# light_bulb_PCB.net
KiCad netlist of a schematic drawn in EAGLE
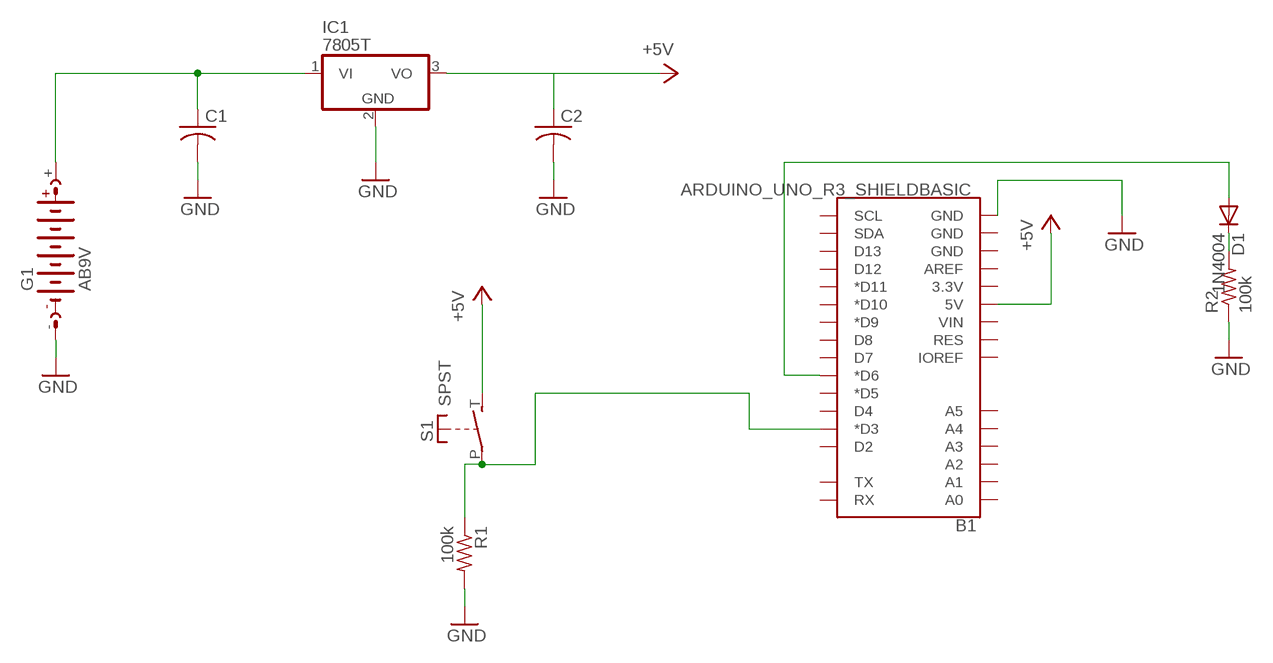
[diagram p0: schematic, sheet 1]

(export (version "E")
  (design (tool "Eeschema 10.0.6"))
  (components
    (comp (ref "B1")
      (value "ARDUINO_UNO_R3_SHIELDBASIC")
      (footprint "eagle-import:UNO_R3_SHIELD")
      (libsource (lib "eagle-import") (part "ARDUINO_UNO_R3_SHIELDBASIC"))
    )
    (comp (ref "C1")
      (value "0.1")
      (footprint "eagle-import:C0805")
      (libsource (lib "eagle-import") (part "C-USC0805"))
    )
    (comp (ref "C2")
      (value "0.1")
      (footprint "eagle-import:C0805")
      (libsource (lib "eagle-import") (part "C-USC0805"))
    )
    (comp (ref "D1")
      (value "1N4004")
      (footprint "eagle-import:DO41-10")
      (libsource (lib "eagle-import") (part "1N4004"))
    )
    (comp (ref "G1")
      (value "AB9V")
      (footprint "eagle-import:AB9V")
      (libsource (lib "eagle-import") (part "AB9V"))
    )
    (comp (ref "IC1")
      (value "7805T")
      (footprint "eagle-import:TO220H")
      (libsource (lib "eagle-import") (part "78T05"))
    )
    (comp (ref "R1")
      (value "100k")
      (footprint "eagle-import:R0805")
      (libsource (lib "eagle-import") (part "R-US_R0805"))
    )
    (comp (ref "R2")
      (value "100k")
      (footprint "eagle-import:R0805")
      (libsource (lib "eagle-import") (part "R-US_R0805"))
    )
    (comp (ref "S1")
      (value "SPST")
      (footprint "eagle-import:JUDCOSPST")
      (libsource (lib "eagle-import") (part "SPST"))
    )
  )
  (nets
    (net (code "1") (name "+5V") (class "Default")
      (node (ref "B1") (pin "5V") (pinfunction "5V_5V") (pintype "bidirectional"))
      (node (ref "C2") (pin "1") (pinfunction "1_1") (pintype "passive"))
      (node (ref "IC1") (pin "3") (pinfunction "VO_3") (pintype "passive"))
      (node (ref "S1") (pin "T") (pinfunction "S_T") (pintype "passive"))
    )
    (net (code "2") (name "GND") (class "Default")
      (node (ref "B1") (pin "GND@0") (pinfunction "GND_GND@0") (pintype "bidirectional"))
      (node (ref "C1") (pin "2") (pinfunction "2_2") (pintype "passive"))
      (node (ref "C2") (pin "2") (pinfunction "2_2") (pintype "passive"))
      (node (ref "G1") (pin "-") (pinfunction "-_-") (pintype "passive"))
      (node (ref "IC1") (pin "2") (pinfunction "GND_2") (pintype "passive"))
      (node (ref "R1") (pin "2") (pinfunction "2_2") (pintype "passive"))
      (node (ref "R2") (pin "1") (pinfunction "1_1") (pintype "passive"))
    )
    (net (code "3") (name "Net-(B1-*D3)") (class "Default")
      (node (ref "B1") (pin "D3") (pinfunction "*D3_D3") (pintype "bidirectional"))
      (node (ref "R1") (pin "1") (pinfunction "1_1") (pintype "passive"))
      (node (ref "S1") (pin "P") (pinfunction "P_P") (pintype "passive"))
    )
    (net (code "4") (name "Net-(B1-*D6)") (class "Default")
      (node (ref "B1") (pin "D6") (pinfunction "*D6_D6") (pintype "bidirectional"))
      (node (ref "D1") (pin "A") (pinfunction "A_A") (pintype "passive"))
    )
    (net (code "5") (name "Net-(D1-PadC)") (class "Default")
      (node (ref "D1") (pin "C") (pinfunction "C_C") (pintype "passive"))
      (node (ref "R2") (pin "2") (pinfunction "2_2") (pintype "passive"))
    )
    (net (code "6") (name "Net-(IC1-VI)") (class "Default")
      (node (ref "C1") (pin "1") (pinfunction "1_1") (pintype "passive"))
      (node (ref "G1") (pin "+") (pinfunction "+_+") (pintype "passive"))
      (node (ref "IC1") (pin "1") (pinfunction "VI_1") (pintype "input"))
    )
    (net (code "7") (name "unconnected-(B1-*D5-PadD5)") (class "Default")
      (node (ref "B1") (pin "D5") (pinfunction "*D5_D5") (pintype "bidirectional"))
    )
    (net (code "8") (name "unconnected-(B1-*D9-PadD9)") (class "Default")
      (node (ref "B1") (pin "D9") (pinfunction "*D9_D9") (pintype "bidirectional"))
    )
    (net (code "9") (name "unconnected-(B1-*D10-PadD10)") (class "Default")
      (node (ref "B1") (pin "D10") (pinfunction "*D10_D10") (pintype "bidirectional"))
    )
    (net (code "10") (name "unconnected-(B1-*D11-PadD11)") (class "Default")
      (node (ref "B1") (pin "D11") (pinfunction "*D11_D11") (pintype "bidirectional"))
    )
    (net (code "11") (name "unconnected-(B1-GND-PadGND@1)") (class "Default")
      (node (ref "B1") (pin "GND@1") (pinfunction "GND_GND@1") (pintype "bidirectional"))
    )
    (net (code "12") (name "unconnected-(B1-GND-PadGND@2)") (class "Default")
      (node (ref "B1") (pin "GND@2") (pinfunction "GND_GND@2") (pintype "bidirectional"))
    )
    (net (code "13") (name "unconnected-(B1-Pad3.3V)") (class "Default")
      (node (ref "B1") (pin "3.3V") (pinfunction "3.3V_3.3V") (pintype "bidirectional"))
    )
    (net (code "14") (name "unconnected-(B1-PadA0)") (class "Default")
      (node (ref "B1") (pin "A0") (pinfunction "A0_A0") (pintype "bidirectional"))
    )
    (net (code "15") (name "unconnected-(B1-PadA1)") (class "Default")
      (node (ref "B1") (pin "A1") (pinfunction "A1_A1") (pintype "bidirectional"))
    )
    (net (code "16") (name "unconnected-(B1-PadA2)") (class "Default")
      (node (ref "B1") (pin "A2") (pinfunction "A2_A2") (pintype "bidirectional"))
    )
    (net (code "17") (name "unconnected-(B1-PadA3)") (class "Default")
      (node (ref "B1") (pin "A3") (pinfunction "A3_A3") (pintype "bidirectional"))
    )
    (net (code "18") (name "unconnected-(B1-PadA4)") (class "Default")
      (node (ref "B1") (pin "A4") (pinfunction "A4_A4") (pintype "bidirectional"))
    )
    (net (code "19") (name "unconnected-(B1-PadA5)") (class "Default")
      (node (ref "B1") (pin "A5") (pinfunction "A5_A5") (pintype "bidirectional"))
    )
    (net (code "20") (name "unconnected-(B1-PadAREF)") (class "Default")
      (node (ref "B1") (pin "AREF") (pinfunction "AREF_AREF") (pintype "bidirectional"))
    )
    (net (code "21") (name "unconnected-(B1-PadD2)") (class "Default")
      (node (ref "B1") (pin "D2") (pinfunction "D2_D2") (pintype "bidirectional"))
    )
    (net (code "22") (name "unconnected-(B1-PadD4)") (class "Default")
      (node (ref "B1") (pin "D4") (pinfunction "D4_D4") (pintype "bidirectional"))
    )
    (net (code "23") (name "unconnected-(B1-PadD7)") (class "Default")
      (node (ref "B1") (pin "D7") (pinfunction "D7_D7") (pintype "bidirectional"))
    )
    (net (code "24") (name "unconnected-(B1-PadD8)") (class "Default")
      (node (ref "B1") (pin "D8") (pinfunction "D8_D8") (pintype "bidirectional"))
    )
    (net (code "25") (name "unconnected-(B1-PadD12)") (class "Default")
      (node (ref "B1") (pin "D12") (pinfunction "D12_D12") (pintype "bidirectional"))
    )
    (net (code "26") (name "unconnected-(B1-PadD13)") (class "Default")
      (node (ref "B1") (pin "D13") (pinfunction "D13_D13") (pintype "bidirectional"))
    )
    (net (code "27") (name "unconnected-(B1-PadIOREF)") (class "Default")
      (node (ref "B1") (pin "IOREF") (pinfunction "IOREF_IOREF") (pintype "bidirectional"))
    )
    (net (code "28") (name "unconnected-(B1-PadRES)") (class "Default")
      (node (ref "B1") (pin "RES") (pinfunction "RES_RES") (pintype "bidirectional"))
    )
    (net (code "29") (name "unconnected-(B1-PadRX)") (class "Default")
      (node (ref "B1") (pin "RX") (pinfunction "RX_RX") (pintype "bidirectional"))
    )
    (net (code "30") (name "unconnected-(B1-PadSCL)") (class "Default")
      (node (ref "B1") (pin "SCL") (pinfunction "SCL_SCL") (pintype "bidirectional"))
    )
    (net (code "31") (name "unconnected-(B1-PadSDA)") (class "Default")
      (node (ref "B1") (pin "SDA") (pinfunction "SDA_SDA") (pintype "bidirectional"))
    )
    (net (code "32") (name "unconnected-(B1-PadTX)") (class "Default")
      (node (ref "B1") (pin "TX") (pinfunction "TX_TX") (pintype "bidirectional"))
    )
    (net (code "33") (name "unconnected-(B1-PadVIN)") (class "Default")
      (node (ref "B1") (pin "VIN") (pinfunction "VIN_VIN") (pintype "bidirectional"))
    )
  )
)
